# 2_-MCU_LPC1759FBD80.net
KiCad netlist of a schematic drawn in Altium Designer
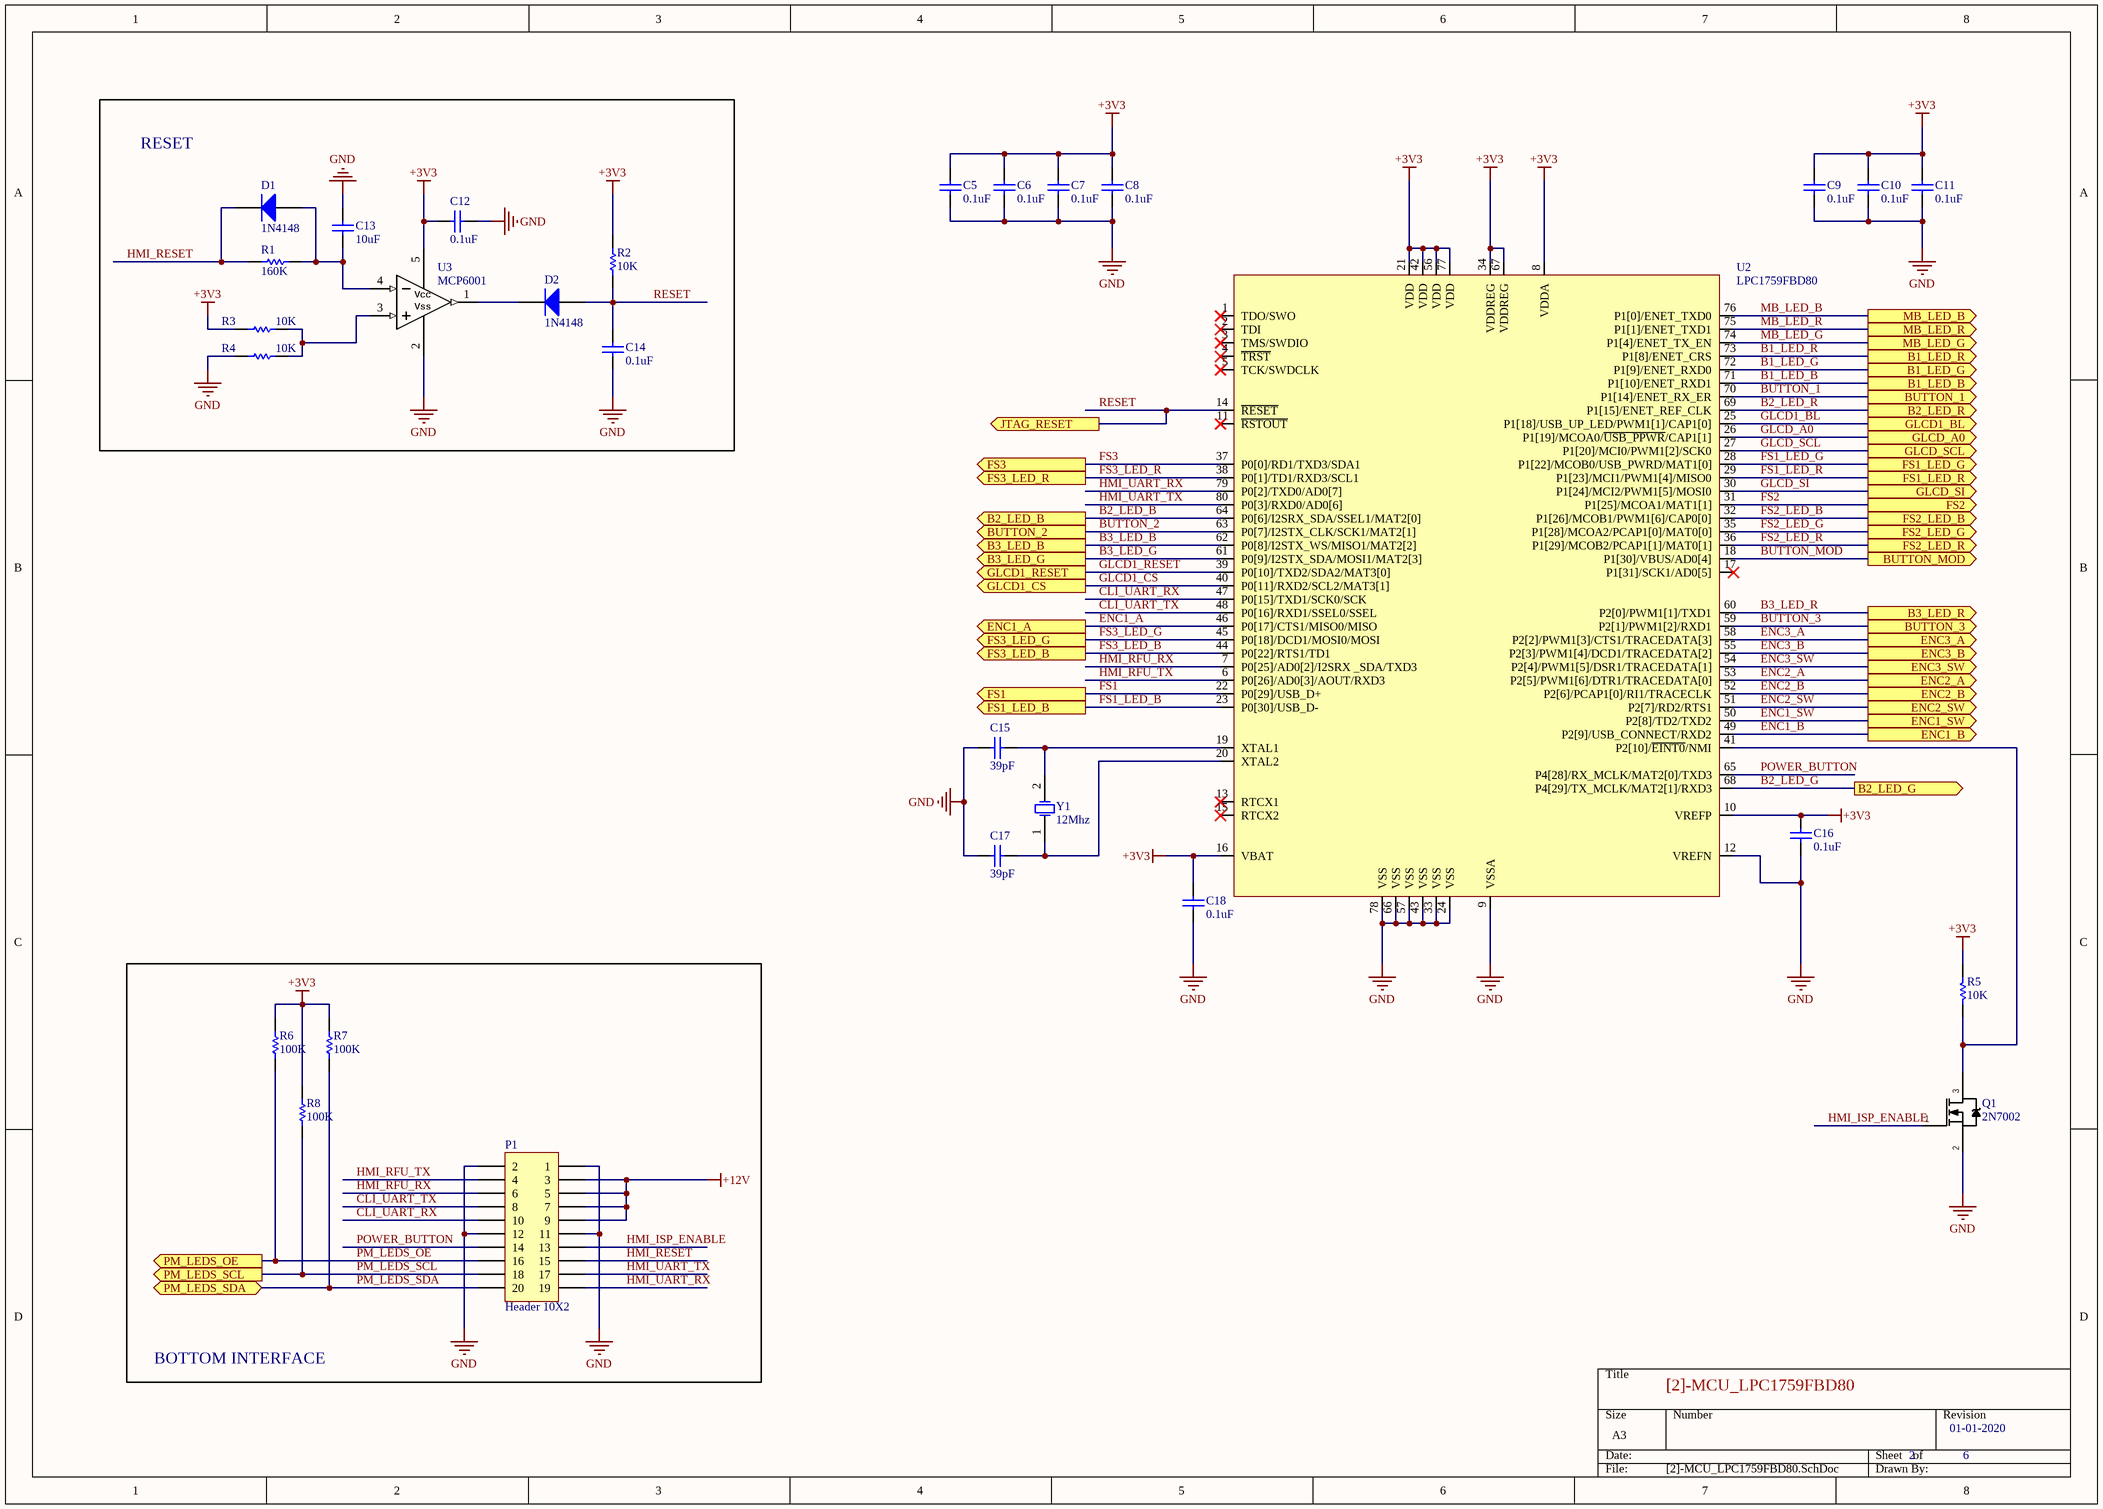
[diagram p0: [2]-MCU_LPC1759FBD80.SchDoc]

(export (version "E")
  (design (tool "Eeschema 10.0.6"))
  (components
    (comp (ref "C5")
      (value "0.1uF")
      (footprint "CAPC1608N")
      (description "CAP CER 0.1UF 25V X7R 0603")
      (fields (field (name "TOLERANCE") "10%") (field (name "VOLTAGE") "25V"))
      (libsource (lib "bitsnio") (part "CC0603KRX7R8BB104"))
    )
    (comp (ref "C6")
      (value "0.1uF")
      (footprint "CAPC1608N")
      (description "CAP CER 0.1UF 25V X7R 0603")
      (fields (field (name "TOLERANCE") "10%") (field (name "VOLTAGE") "25V"))
      (libsource (lib "bitsnio") (part "CC0603KRX7R8BB104"))
    )
    (comp (ref "C7")
      (value "0.1uF")
      (footprint "CAPC1608N")
      (description "CAP CER 0.1UF 25V X7R 0603")
      (fields (field (name "TOLERANCE") "10%") (field (name "VOLTAGE") "25V"))
      (libsource (lib "bitsnio") (part "CC0603KRX7R8BB104"))
    )
    (comp (ref "C8")
      (value "0.1uF")
      (footprint "CAPC1608N")
      (description "CAP CER 0.1UF 25V X7R 0603")
      (fields (field (name "TOLERANCE") "10%") (field (name "VOLTAGE") "25V"))
      (libsource (lib "bitsnio") (part "CC0603KRX7R8BB104"))
    )
    (comp (ref "C9")
      (value "0.1uF")
      (footprint "CAPC1608N")
      (description "CAP CER 0.1UF 25V X7R 0603")
      (fields (field (name "TOLERANCE") "10%") (field (name "VOLTAGE") "25V"))
      (libsource (lib "bitsnio") (part "CC0603KRX7R8BB104"))
    )
    (comp (ref "C10")
      (value "0.1uF")
      (footprint "CAPC1608N")
      (description "CAP CER 0.1UF 25V X7R 0603")
      (fields (field (name "TOLERANCE") "10%") (field (name "VOLTAGE") "25V"))
      (libsource (lib "bitsnio") (part "CC0603KRX7R8BB104"))
    )
    (comp (ref "C11")
      (value "0.1uF")
      (footprint "CAPC1608N")
      (description "CAP CER 0.1UF 25V X7R 0603")
      (fields (field (name "TOLERANCE") "10%") (field (name "VOLTAGE") "25V"))
      (libsource (lib "bitsnio") (part "CC0603KRX7R8BB104"))
    )
    (comp (ref "C12")
      (value "0.1uF")
      (footprint "CAPC1608N")
      (description "CAP CER 0.1UF 25V X7R 0603")
      (fields (field (name "TOLERANCE") "10%") (field (name "VOLTAGE") "25V"))
      (libsource (lib "bitsnio") (part "CC0603KRX7R8BB104"))
    )
    (comp (ref "C13")
      (value "10uF")
      (footprint "CAPC1608N")
      (description "CAP CER 10UF 10V X5R 0603")
      (fields (field (name "TOLERANCE") "10%") (field (name "VOLTAGE") "10V"))
      (libsource (lib "bitsnio") (part "GRM188R61A106KE69D"))
    )
    (comp (ref "C14")
      (value "0.1uF")
      (footprint "CAPC1608N")
      (description "CAP CER 0.1UF 25V X7R 0603")
      (fields (field (name "TOLERANCE") "10%") (field (name "VOLTAGE") "25V"))
      (libsource (lib "bitsnio") (part "CC0603KRX7R8BB104"))
    )
    (comp (ref "C15")
      (value "39pF")
      (footprint "CAPC1608N")
      (description "CAP CER 39PF 50V NP0 0603")
      (fields (field (name "TOLERANCE") "5%"))
      (libsource (lib "bitsnio") (part "C1608NP01H390J080AA"))
    )
    (comp (ref "C16")
      (value "0.1uF")
      (footprint "CAPC1608N")
      (description "CAP CER 0.1UF 25V X7R 0603")
      (fields (field (name "TOLERANCE") "10%") (field (name "VOLTAGE") "25V"))
      (libsource (lib "bitsnio") (part "CC0603KRX7R8BB104"))
    )
    (comp (ref "C17")
      (value "39pF")
      (footprint "CAPC1608N")
      (description "CAP CER 39PF 50V NP0 0603")
      (fields (field (name "TOLERANCE") "5%"))
      (libsource (lib "bitsnio") (part "C1608NP01H390J080AA"))
    )
    (comp (ref "C18")
      (value "0.1uF")
      (footprint "CAPC1608N")
      (description "CAP CER 0.1UF 25V X7R 0603")
      (fields (field (name "TOLERANCE") "10%") (field (name "VOLTAGE") "25V"))
      (libsource (lib "bitsnio") (part "CC0603KRX7R8BB104"))
    )
    (comp (ref "D1")
      (value "1N4148")
      (footprint "SOD-323")
      (description "DIODE SWITCHING 75V 0.15A SOD323")
      (fields (field (name "VOLTAGE") "75V"))
      (libsource (lib "bitsnio") (part "1N4148WS-7-F"))
    )
    (comp (ref "D2")
      (value "1N4148")
      (footprint "SOD-323")
      (description "DIODE SWITCHING 75V 0.15A SOD323")
      (fields (field (name "VOLTAGE") "75V"))
      (libsource (lib "bitsnio") (part "1N4148WS-7-F"))
    )
    (comp (ref "P1")
      (value "Header 10X2")
      (footprint "HDR2X10")
      (description "Header, 10-Pin, Dual row")
      (fields (field (name "PUBLISHER") "Altium Limited"))
      (libsource (lib "Miscellaneous Connectors") (part "Header 10X2"))
    )
    (comp (ref "Q1")
      (value "2N7002")
      (footprint "SOT23-3N")
      (description "MOSFET N-CH 60V 115MA SOT-23")
      (fields (field (name "VOLTAGE") "60V"))
      (libsource (lib "bitsnio") (part "2N7002"))
    )
    (comp (ref "R1")
      (value "160K")
      (footprint "RESC1608N")
      (description "RES SMD 160K OHM 5% 1/10W 0603")
      (fields (field (name "TOLERANCE") "5%"))
      (libsource (lib "bitsnio") (part "RMCF0603JT160K"))
    )
    (comp (ref "R2")
      (value "10K")
      (footprint "RESC1608N")
      (description "RES SMD 10K OHM 5% 1/10W 0603")
      (fields (field (name "TOLERANCE") "5%"))
      (libsource (lib "bitsnio") (part "AC0603JR-0710KL"))
    )
    (comp (ref "R3")
      (value "10K")
      (footprint "RESC1608N")
      (description "RES SMD 10K OHM 5% 1/10W 0603")
      (fields (field (name "TOLERANCE") "5%"))
      (libsource (lib "bitsnio") (part "AC0603JR-0710KL"))
    )
    (comp (ref "R4")
      (value "10K")
      (footprint "RESC1608N")
      (description "RES SMD 10K OHM 5% 1/10W 0603")
      (fields (field (name "TOLERANCE") "5%"))
      (libsource (lib "bitsnio") (part "AC0603JR-0710KL"))
    )
    (comp (ref "R5")
      (value "10K")
      (footprint "RESC1608N")
      (description "RES SMD 10K OHM 5% 1/10W 0603")
      (fields (field (name "TOLERANCE") "5%"))
      (libsource (lib "bitsnio") (part "AC0603JR-0710KL"))
    )
    (comp (ref "R6")
      (value "100K")
      (footprint "RESC1608N")
      (description "RES SMD 100K OHM 5% 1/4W 0603")
      (fields (field (name "TOLERANCE") "5%"))
      (libsource (lib "bitsnio") (part "ESR03EZPJ104"))
    )
    (comp (ref "R7")
      (value "100K")
      (footprint "RESC1608N")
      (description "RES SMD 100K OHM 5% 1/4W 0603")
      (fields (field (name "TOLERANCE") "5%"))
      (libsource (lib "bitsnio") (part "ESR03EZPJ104"))
    )
    (comp (ref "R8")
      (value "100K")
      (footprint "RESC1608N")
      (description "RES SMD 100K OHM 5% 1/4W 0603")
      (fields (field (name "TOLERANCE") "5%"))
      (libsource (lib "bitsnio") (part "ESR03EZPJ104"))
    )
    (comp (ref "U2")
      (value "LPC1759FBD80")
      (footprint "LQFP80")
      (description "IC MCU 32BIT 512KB FLASH 80LQFP")
      (libsource (lib "bitsnio") (part "IC_LPC1759FBD80,551"))
    )
    (comp (ref "U3")
      (value "MCP6001")
      (footprint "SOT23-5N")
      (description "IC OPAMP GP 1MHZ RRO SOT23-5")
      (fields (field (name "VOLTAGE") "6V"))
      (libsource (lib "bitsnio") (part "IC_MCP6001T-I/OT"))
    )
    (comp (ref "Y1")
      (value "12Mhz")
      (footprint "CRYSTAL_HC49SDLF")
      (description "CRYSTAL 12.0000MHZ 20PF SMD")
      (libsource (lib "bitsnio") (part "FC4SDCBMF12.0-T1"))
    )
  )
  (nets
    (net (code "1") (name "+3V3") (class "Default")
      (node (ref "C10") (pin "2") (pinfunction "2_2") (pintype "passive"))
      (node (ref "C11") (pin "2") (pinfunction "2_2") (pintype "passive"))
      (node (ref "C12") (pin "2") (pinfunction "2_2") (pintype "passive"))
      (node (ref "C16") (pin "2") (pinfunction "2_2") (pintype "passive"))
      (node (ref "C18") (pin "2") (pinfunction "2_2") (pintype "passive"))
      (node (ref "C5") (pin "2") (pinfunction "2_2") (pintype "passive"))
      (node (ref "C6") (pin "2") (pinfunction "2_2") (pintype "passive"))
      (node (ref "C7") (pin "2") (pinfunction "2_2") (pintype "passive"))
      (node (ref "C8") (pin "2") (pinfunction "2_2") (pintype "passive"))
      (node (ref "C9") (pin "2") (pinfunction "2_2") (pintype "passive"))
      (node (ref "R2") (pin "1") (pinfunction "1_1") (pintype "passive"))
      (node (ref "R3") (pin "2") (pinfunction "2_2") (pintype "passive"))
      (node (ref "R5") (pin "1") (pinfunction "1_1") (pintype "passive"))
      (node (ref "R6") (pin "2") (pinfunction "2_2") (pintype "passive"))
      (node (ref "R7") (pin "2") (pinfunction "2_2") (pintype "passive"))
      (node (ref "R8") (pin "2") (pinfunction "2_2") (pintype "passive"))
      (node (ref "U2") (pin "10") (pinfunction "VREFP_10") (pintype "passive"))
      (node (ref "U2") (pin "16") (pinfunction "VBAT_16") (pintype "passive"))
      (node (ref "U2") (pin "21") (pinfunction "VDD_21") (pintype "passive"))
      (node (ref "U2") (pin "34") (pinfunction "VDDREG_34") (pintype "passive"))
      (node (ref "U2") (pin "42") (pinfunction "VDD_42") (pintype "passive"))
      (node (ref "U2") (pin "56") (pinfunction "VDD_56") (pintype "passive"))
      (node (ref "U2") (pin "67") (pinfunction "VDDREG_67") (pintype "passive"))
      (node (ref "U2") (pin "77") (pinfunction "VDD_77") (pintype "passive"))
      (node (ref "U2") (pin "8") (pinfunction "VDDA_8") (pintype "passive"))
      (node (ref "U3") (pin "5") (pinfunction "VCC_5") (pintype "power_in"))
    )
    (net (code "2") (name "+12V") (class "Default")
      (node (ref "P1") (pin "3") (pinfunction "3_3") (pintype "passive"))
      (node (ref "P1") (pin "5") (pinfunction "5_5") (pintype "passive"))
      (node (ref "P1") (pin "7") (pinfunction "7_7") (pintype "passive"))
      (node (ref "P1") (pin "9") (pinfunction "9_9") (pintype "passive"))
    )
    (net (code "3") (name "/B1_LED_B") (class "Default")
      (node (ref "U2") (pin "71") (pinfunction "P1[10]/ENET_RXD1_71") (pintype "passive"))
    )
    (net (code "4") (name "/B1_LED_G") (class "Default")
      (node (ref "U2") (pin "72") (pinfunction "P1[9]/ENET_RXD0_72") (pintype "passive"))
    )
    (net (code "5") (name "/B1_LED_R") (class "Default")
      (node (ref "U2") (pin "73") (pinfunction "P1[8]/ENET_CRS_73") (pintype "passive"))
    )
    (net (code "6") (name "/B2_LED_B") (class "Default")
      (node (ref "U2") (pin "64") (pinfunction "P0[6]/I2SRX_SDA/SSEL1/MAT2[0]_64") (pintype "passive"))
    )
    (net (code "7") (name "/B2_LED_G") (class "Default")
      (node (ref "U2") (pin "68") (pinfunction "P4[29]/TX_MCLK/MAT2[1]/RXD3_68") (pintype "passive"))
    )
    (net (code "8") (name "/B2_LED_R") (class "Default")
      (node (ref "U2") (pin "69") (pinfunction "P1[15]/ENET_REF_CLK_69") (pintype "passive"))
    )
    (net (code "9") (name "/B3_LED_B") (class "Default")
      (node (ref "U2") (pin "62") (pinfunction "P0[8]/I2STX_WS/MISO1/MAT2[2]_62") (pintype "passive"))
    )
    (net (code "10") (name "/B3_LED_G") (class "Default")
      (node (ref "U2") (pin "61") (pinfunction "P0[9]/I2STX_SDA/MOSI1/MAT2[3]_61") (pintype "passive"))
    )
    (net (code "11") (name "/B3_LED_R") (class "Default")
      (node (ref "U2") (pin "60") (pinfunction "P2[0]/PWM1[1]/TXD1_60") (pintype "passive"))
    )
    (net (code "12") (name "/BUTTON_1") (class "Default")
      (node (ref "U2") (pin "70") (pinfunction "P1[14]/ENET_RX_ER_70") (pintype "passive"))
    )
    (net (code "13") (name "/BUTTON_2") (class "Default")
      (node (ref "U2") (pin "63") (pinfunction "P0[7]/I2STX_CLK/SCK1/MAT2[1]_63") (pintype "passive"))
    )
    (net (code "14") (name "/BUTTON_3") (class "Default")
      (node (ref "U2") (pin "59") (pinfunction "P2[1]/PWM1[2]/RXD1_59") (pintype "passive"))
    )
    (net (code "15") (name "/BUTTON_MOD") (class "Default")
      (node (ref "U2") (pin "18") (pinfunction "P1[30]/VBUS/AD0[4]_18") (pintype "passive"))
    )
    (net (code "16") (name "/CLI_UART_RX") (class "Default")
      (node (ref "P1") (pin "10") (pinfunction "10_10") (pintype "passive"))
      (node (ref "U2") (pin "47") (pinfunction "P0[15]/TXD1/SCK0/SCK_47") (pintype "passive"))
    )
    (net (code "17") (name "/CLI_UART_TX") (class "Default")
      (node (ref "P1") (pin "8") (pinfunction "8_8") (pintype "passive"))
      (node (ref "U2") (pin "48") (pinfunction "P0[16]/RXD1/SSEL0/SSEL_48") (pintype "passive"))
    )
    (net (code "18") (name "/ENC1_A") (class "Default")
      (node (ref "U2") (pin "46") (pinfunction "P0[17]/CTS1/MISO0/MISO_46") (pintype "passive"))
    )
    (net (code "19") (name "/ENC1_B") (class "Default")
      (node (ref "U2") (pin "49") (pinfunction "P2[9]/USB_CONNECT/RXD2_49") (pintype "passive"))
    )
    (net (code "20") (name "/ENC1_SW") (class "Default")
      (node (ref "U2") (pin "50") (pinfunction "P2[8]/TD2/TXD2_50") (pintype "passive"))
    )
    (net (code "21") (name "/ENC2_A") (class "Default")
      (node (ref "U2") (pin "53") (pinfunction "P2[5]/PWM1[6]/DTR1/TRACEDATA[0]_53") (pintype "passive"))
    )
    (net (code "22") (name "/ENC2_B") (class "Default")
      (node (ref "U2") (pin "52") (pinfunction "P2[6]/PCAP1[0]/RI1/TRACECLK_52") (pintype "passive"))
    )
    (net (code "23") (name "/ENC2_SW") (class "Default")
      (node (ref "U2") (pin "51") (pinfunction "P2[7]/RD2/RTS1_51") (pintype "passive"))
    )
    (net (code "24") (name "/ENC3_A") (class "Default")
      (node (ref "U2") (pin "58") (pinfunction "P2[2]/PWM1[3]/CTS1/TRACEDATA[3]_58") (pintype "passive"))
    )
    (net (code "25") (name "/ENC3_B") (class "Default")
      (node (ref "U2") (pin "55") (pinfunction "P2[3]/PWM1[4]/DCD1/TRACEDATA[2]_55") (pintype "passive"))
    )
    (net (code "26") (name "/ENC3_SW") (class "Default")
      (node (ref "U2") (pin "54") (pinfunction "P2[4]/PWM1[5]/DSR1/TRACEDATA[1]_54") (pintype "passive"))
    )
    (net (code "27") (name "/FS1") (class "Default")
      (node (ref "U2") (pin "22") (pinfunction "P0[29]/USB_D+_22") (pintype "passive"))
    )
    (net (code "28") (name "/FS1_LED_B") (class "Default")
      (node (ref "U2") (pin "23") (pinfunction "P0[30]/USB_D-_23") (pintype "passive"))
    )
    (net (code "29") (name "/FS1_LED_G") (class "Default")
      (node (ref "U2") (pin "28") (pinfunction "P1[22]/MCOB0/USB_PWRD/MAT1[0]_28") (pintype "passive"))
    )
    (net (code "30") (name "/FS1_LED_R") (class "Default")
      (node (ref "U2") (pin "29") (pinfunction "P1[23]/MCI1/PWM1[4]/MISO0_29") (pintype "passive"))
    )
    (net (code "31") (name "/FS2") (class "Default")
      (node (ref "U2") (pin "31") (pinfunction "P1[25]/MCOA1/MAT1[1]_31") (pintype "passive"))
    )
    (net (code "32") (name "/FS2_LED_B") (class "Default")
      (node (ref "U2") (pin "32") (pinfunction "P1[26]/MCOB1/PWM1[6]/CAP0[0]_32") (pintype "passive"))
    )
    (net (code "33") (name "/FS2_LED_G") (class "Default")
      (node (ref "U2") (pin "35") (pinfunction "P1[28]/MCOA2/PCAP1[0]/MAT0[0]_35") (pintype "passive"))
    )
    (net (code "34") (name "/FS2_LED_R") (class "Default")
      (node (ref "U2") (pin "36") (pinfunction "P1[29]/MCOB2/PCAP1[1]/MAT0[1]_36") (pintype "passive"))
    )
    (net (code "35") (name "/FS3") (class "Default")
      (node (ref "U2") (pin "37") (pinfunction "P0[0]/RD1/TXD3/SDA1_37") (pintype "passive"))
    )
    (net (code "36") (name "/FS3_LED_B") (class "Default")
      (node (ref "U2") (pin "44") (pinfunction "P0[22]/RTS1/TD1_44") (pintype "passive"))
    )
    (net (code "37") (name "/FS3_LED_G") (class "Default")
      (node (ref "U2") (pin "45") (pinfunction "P0[18]/DCD1/MOSI0/MOSI_45") (pintype "passive"))
    )
    (net (code "38") (name "/FS3_LED_R") (class "Default")
      (node (ref "U2") (pin "38") (pinfunction "P0[1]/TD1/RXD3/SCL1_38") (pintype "passive"))
    )
    (net (code "39") (name "/GLCD1_BL") (class "Default")
      (node (ref "U2") (pin "25") (pinfunction "P1[18]/USB_UP_LED/PWM1[1]/CAP1[0]_25") (pintype "passive"))
    )
    (net (code "40") (name "/GLCD1_CS") (class "Default")
      (node (ref "U2") (pin "40") (pinfunction "P0[11]/RXD2/SCL2/MAT3[1]_40") (pintype "passive"))
    )
    (net (code "41") (name "/GLCD1_RESET") (class "Default")
      (node (ref "U2") (pin "39") (pinfunction "P0[10]/TXD2/SDA2/MAT3[0]_39") (pintype "passive"))
    )
    (net (code "42") (name "/GLCD_A0") (class "Default")
      (node (ref "U2") (pin "26") (pinfunction "P1[19]/MCOA0/~{USB_PPWR}/CAP1[1]_26") (pintype "passive"))
    )
    (net (code "43") (name "/GLCD_SCL") (class "Default")
      (node (ref "U2") (pin "27") (pinfunction "P1[20]/MCI0/PWM1[2]/SCK0_27") (pintype "passive"))
    )
    (net (code "44") (name "/GLCD_SI") (class "Default")
      (node (ref "U2") (pin "30") (pinfunction "P1[24]/MCI2/PWM1[5]/MOSI0_30") (pintype "passive"))
    )
    (net (code "45") (name "/HMI_ISP_ENABLE") (class "Default")
      (node (ref "P1") (pin "13") (pinfunction "13_13") (pintype "passive"))
      (node (ref "Q1") (pin "1") (pinfunction "G_1") (pintype "passive"))
    )
    (net (code "46") (name "/HMI_RESET") (class "Default")
      (node (ref "D1") (pin "1") (pinfunction "K_1") (pintype "passive"))
      (node (ref "P1") (pin "15") (pinfunction "15_15") (pintype "passive"))
      (node (ref "R1") (pin "1") (pinfunction "1_1") (pintype "passive"))
    )
    (net (code "47") (name "/HMI_RFU_RX") (class "Default")
      (node (ref "P1") (pin "6") (pinfunction "6_6") (pintype "passive"))
      (node (ref "U2") (pin "7") (pinfunction "P0[25]/AD0[2]/I2SRX__SDA/TXD3_7") (pintype "passive"))
    )
    (net (code "48") (name "/HMI_RFU_TX") (class "Default")
      (node (ref "P1") (pin "4") (pinfunction "4_4") (pintype "passive"))
      (node (ref "U2") (pin "6") (pinfunction "P0[26]/AD0[3]/AOUT/RXD3_6") (pintype "passive"))
    )
    (net (code "49") (name "/HMI_UART_RX") (class "Default")
      (node (ref "P1") (pin "19") (pinfunction "19_19") (pintype "passive"))
      (node (ref "U2") (pin "79") (pinfunction "P0[2]/TXD0/AD0[7]_79") (pintype "passive"))
    )
    (net (code "50") (name "/HMI_UART_TX") (class "Default")
      (node (ref "P1") (pin "17") (pinfunction "17_17") (pintype "passive"))
      (node (ref "U2") (pin "80") (pinfunction "P0[3]/RXD0/AD0[6]_80") (pintype "passive"))
    )
    (net (code "51") (name "/MB_LED_B") (class "Default")
      (node (ref "U2") (pin "76") (pinfunction "P1[0]/ENET_TXD0_76") (pintype "passive"))
    )
    (net (code "52") (name "/MB_LED_G") (class "Default")
      (node (ref "U2") (pin "74") (pinfunction "P1[4]/ENET_TX_EN_74") (pintype "passive"))
    )
    (net (code "53") (name "/MB_LED_R") (class "Default")
      (node (ref "U2") (pin "75") (pinfunction "P1[1]/ENET_TXD1_75") (pintype "passive"))
    )
    (net (code "54") (name "/PM_LEDS_OE") (class "Default")
      (node (ref "P1") (pin "16") (pinfunction "16_16") (pintype "passive"))
      (node (ref "R6") (pin "1") (pinfunction "1_1") (pintype "passive"))
    )
    (net (code "55") (name "/PM_LEDS_SCL") (class "Default")
      (node (ref "P1") (pin "18") (pinfunction "18_18") (pintype "passive"))
      (node (ref "R8") (pin "1") (pinfunction "1_1") (pintype "passive"))
    )
    (net (code "56") (name "/PM_LEDS_SDA") (class "Default")
      (node (ref "P1") (pin "20") (pinfunction "20_20") (pintype "passive"))
      (node (ref "R7") (pin "1") (pinfunction "1_1") (pintype "passive"))
    )
    (net (code "57") (name "/POWER_BUTTON") (class "Default")
      (node (ref "P1") (pin "14") (pinfunction "14_14") (pintype "passive"))
      (node (ref "U2") (pin "65") (pinfunction "P4[28]/RX_MCLK/MAT2[0]/TXD3_65") (pintype "passive"))
    )
    (net (code "58") (name "/RESET") (class "Default")
      (node (ref "C14") (pin "1") (pinfunction "1_1") (pintype "passive"))
      (node (ref "D2") (pin "2") (pinfunction "A_2") (pintype "passive"))
      (node (ref "R2") (pin "2") (pinfunction "2_2") (pintype "passive"))
      (node (ref "U2") (pin "14") (pinfunction "~{RESET}_14") (pintype "passive"))
    )
    (net (code "59") (name "GND") (class "Default")
      (node (ref "C10") (pin "1") (pinfunction "1_1") (pintype "passive"))
      (node (ref "C11") (pin "1") (pinfunction "1_1") (pintype "passive"))
      (node (ref "C12") (pin "1") (pinfunction "1_1") (pintype "passive"))
      (node (ref "C13") (pin "1") (pinfunction "1_1") (pintype "passive"))
      (node (ref "C14") (pin "2") (pinfunction "2_2") (pintype "passive"))
      (node (ref "C15") (pin "2") (pinfunction "2_2") (pintype "passive"))
      (node (ref "C16") (pin "1") (pinfunction "1_1") (pintype "passive"))
      (node (ref "C17") (pin "1") (pinfunction "1_1") (pintype "passive"))
      (node (ref "C18") (pin "1") (pinfunction "1_1") (pintype "passive"))
      (node (ref "C5") (pin "1") (pinfunction "1_1") (pintype "passive"))
      (node (ref "C6") (pin "1") (pinfunction "1_1") (pintype "passive"))
      (node (ref "C7") (pin "1") (pinfunction "1_1") (pintype "passive"))
      (node (ref "C8") (pin "1") (pinfunction "1_1") (pintype "passive"))
      (node (ref "C9") (pin "1") (pinfunction "1_1") (pintype "passive"))
      (node (ref "P1") (pin "1") (pinfunction "1_1") (pintype "passive"))
      (node (ref "P1") (pin "11") (pinfunction "11_11") (pintype "passive"))
      (node (ref "P1") (pin "12") (pinfunction "12_12") (pintype "passive"))
      (node (ref "P1") (pin "2") (pinfunction "2_2") (pintype "passive"))
      (node (ref "Q1") (pin "2") (pinfunction "S_2") (pintype "passive"))
      (node (ref "R4") (pin "2") (pinfunction "2_2") (pintype "passive"))
      (node (ref "U2") (pin "12") (pinfunction "VREFN_12") (pintype "passive"))
      (node (ref "U2") (pin "24") (pinfunction "VSS_24") (pintype "passive"))
      (node (ref "U2") (pin "33") (pinfunction "VSS_33") (pintype "passive"))
      (node (ref "U2") (pin "43") (pinfunction "VSS_43") (pintype "passive"))
      (node (ref "U2") (pin "57") (pinfunction "VSS_57") (pintype "passive"))
      (node (ref "U2") (pin "66") (pinfunction "VSS_66") (pintype "passive"))
      (node (ref "U2") (pin "78") (pinfunction "VSS_78") (pintype "passive"))
      (node (ref "U2") (pin "9") (pinfunction "VSSA_9") (pintype "passive"))
      (node (ref "U3") (pin "2") (pinfunction "VSS_2") (pintype "power_in"))
    )
    (net (code "60") (name "Net-(D1-A)") (class "Default")
      (node (ref "C13") (pin "2") (pinfunction "2_2") (pintype "passive"))
      (node (ref "D1") (pin "2") (pinfunction "A_2") (pintype "passive"))
      (node (ref "R1") (pin "2") (pinfunction "2_2") (pintype "passive"))
      (node (ref "U3") (pin "4") (pinfunction "IN-_4") (pintype "input"))
    )
    (net (code "61") (name "Net-(D2-K)") (class "Default")
      (node (ref "D2") (pin "1") (pinfunction "K_1") (pintype "passive"))
      (node (ref "U3") (pin "1") (pinfunction "OUT_1") (pintype "output"))
    )
    (net (code "62") (name "Net-(Q1-D)") (class "Default")
      (node (ref "Q1") (pin "3") (pinfunction "D_3") (pintype "passive"))
      (node (ref "R5") (pin "2") (pinfunction "2_2") (pintype "passive"))
      (node (ref "U2") (pin "41") (pinfunction "P2[10]/~{EINT0}/NMI_41") (pintype "passive"))
    )
    (net (code "63") (name "Net-(U2-XTAL1)") (class "Default")
      (node (ref "C15") (pin "1") (pinfunction "1_1") (pintype "passive"))
      (node (ref "U2") (pin "19") (pinfunction "XTAL1_19") (pintype "passive"))
      (node (ref "Y1") (pin "2") (pinfunction "OSC2_2") (pintype "passive"))
    )
    (net (code "64") (name "Net-(U2-XTAL2)") (class "Default")
      (node (ref "C17") (pin "2") (pinfunction "2_2") (pintype "passive"))
      (node (ref "U2") (pin "20") (pinfunction "XTAL2_20") (pintype "passive"))
      (node (ref "Y1") (pin "1") (pinfunction "OSC1_1") (pintype "passive"))
    )
    (net (code "65") (name "Net-(U3-IN+)") (class "Default")
      (node (ref "R3") (pin "1") (pinfunction "1_1") (pintype "passive"))
      (node (ref "R4") (pin "1") (pinfunction "1_1") (pintype "passive"))
      (node (ref "U3") (pin "3") (pinfunction "IN+_3") (pintype "input"))
    )
    (net (code "66") (name "unconnected-(U2-P1[31]{slash}SCK1{slash}AD0[5]-Pad17)") (class "Default")
      (node (ref "U2") (pin "17") (pinfunction "P1[31]/SCK1/AD0[5]_17") (pintype "passive+no_connect"))
    )
    (net (code "67") (name "unconnected-(U2-RTCX1-Pad13)") (class "Default")
      (node (ref "U2") (pin "13") (pinfunction "RTCX1_13") (pintype "passive+no_connect"))
    )
    (net (code "68") (name "unconnected-(U2-RTCX2-Pad15)") (class "Default")
      (node (ref "U2") (pin "15") (pinfunction "RTCX2_15") (pintype "passive+no_connect"))
    )
    (net (code "69") (name "unconnected-(U2-TCK{slash}SWDCLK-Pad5)") (class "Default")
      (node (ref "U2") (pin "5") (pinfunction "TCK/SWDCLK_5") (pintype "passive+no_connect"))
    )
    (net (code "70") (name "unconnected-(U2-TDI-Pad2)") (class "Default")
      (node (ref "U2") (pin "2") (pinfunction "TDI_2") (pintype "passive+no_connect"))
    )
    (net (code "71") (name "unconnected-(U2-TDO{slash}SWO-Pad1)") (class "Default")
      (node (ref "U2") (pin "1") (pinfunction "TDO/SWO_1") (pintype "passive+no_connect"))
    )
    (net (code "72") (name "unconnected-(U2-TMS{slash}SWDIO-Pad3)") (class "Default")
      (node (ref "U2") (pin "3") (pinfunction "TMS/SWDIO_3") (pintype "passive+no_connect"))
    )
    (net (code "73") (name "unconnected-(U2-~{RSTOUT}-Pad11)") (class "Default")
      (node (ref "U2") (pin "11") (pinfunction "~{RSTOUT}_11") (pintype "passive+no_connect"))
    )
    (net (code "74") (name "unconnected-(U2-~{TRST}-Pad4)") (class "Default")
      (node (ref "U2") (pin "4") (pinfunction "~{TRST}_4") (pintype "passive+no_connect"))
    )
  )
)
